# EFuse_12V.net
KiCad netlist of a schematic drawn in Altium Designer
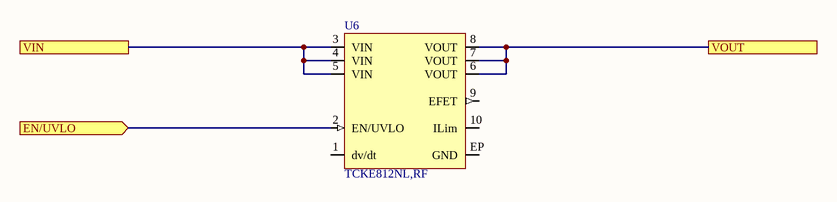
[diagram p0: EFuse_12V.SchDoc]

(export (version "E")
  (design (tool "Eeschema 10.0.6"))
  (components
    (comp (ref "U6")
      (value "TCKE812NL,RF")
      (footprint "WSON10B-Toshiba")
      (description "Fuse IC with Adjustable Over Current Protection and Reverse Current Blocking FET Control")
      (libsource (lib "AFR365") (part "TCKE812NL,RF"))
    )
  )
  (nets
    (net (code "1") (name "/EN{slash}UVLO") (class "Default")
      (node (ref "U6") (pin "2") (pinfunction "EN/UVLO_2") (pintype "input"))
    )
    (net (code "2") (name "/VIN") (class "Default")
      (node (ref "U6") (pin "3") (pinfunction "VIN_3") (pintype "power_in"))
      (node (ref "U6") (pin "4") (pinfunction "VIN_4") (pintype "power_in"))
      (node (ref "U6") (pin "5") (pinfunction "VIN_5") (pintype "power_in"))
    )
    (net (code "3") (name "/VOUT") (class "Default")
      (node (ref "U6") (pin "6") (pinfunction "VOUT_6") (pintype "power_in"))
      (node (ref "U6") (pin "7") (pinfunction "VOUT_7") (pintype "power_in"))
      (node (ref "U6") (pin "8") (pinfunction "VOUT_8") (pintype "power_in"))
    )
    (net (code "4") (name "unconnected-(U6-EFET-Pad9)") (class "Default")
      (node (ref "U6") (pin "9") (pinfunction "EFET_9") (pintype "output"))
    )
    (net (code "5") (name "unconnected-(U6-GND-PadEP)") (class "Default")
      (node (ref "U6") (pin "EP") (pinfunction "GND_EP") (pintype "passive"))
    )
    (net (code "6") (name "unconnected-(U6-ILim-Pad10)") (class "Default")
      (node (ref "U6") (pin "10") (pinfunction "ILim_10") (pintype "passive"))
    )
    (net (code "7") (name "unconnected-(U6-dv{slash}dt-Pad1)") (class "Default")
      (node (ref "U6") (pin "1") (pinfunction "dv/dt_1") (pintype "passive"))
    )
  )
)
